# TTL_USB.net
KiCad netlist of a schematic drawn in Altium Designer
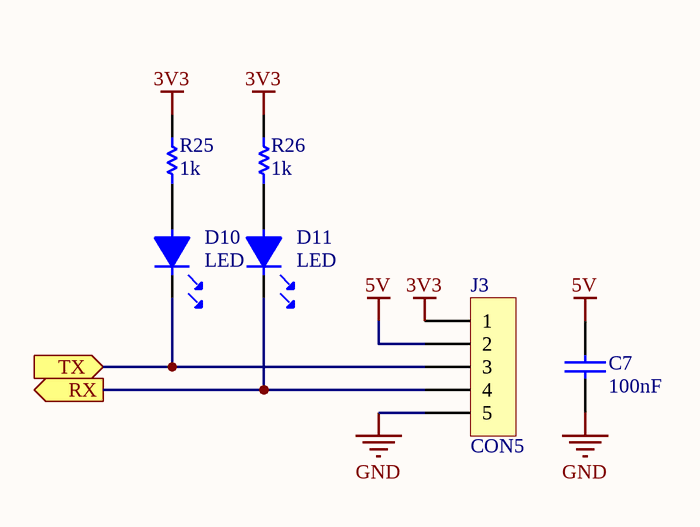
[diagram p0: TTL USB.SchDoc]

(export (version "E")
  (design (tool "Eeschema 10.0.6"))
  (components
    (comp (ref "C7") (value "100nF") (footprint "0805") (libsource (lib "LIBPIOIX") (part "CAP")))
    (comp (ref "D10") (value "LED") (footprint "LED0805") (libsource (lib "LIBPIOIX") (part "LED")))
    (comp (ref "D11") (value "LED") (footprint "LED0805") (libsource (lib "LIBPIOIX") (part "LED")))
    (comp (ref "J3") (value "CON5") (footprint "SIP5") (libsource (lib "LIBPIOIX") (part "CON5")))
    (comp (ref "R25") (value "1k") (footprint "0805") (libsource (lib "LIBPIOIX") (part "RES")))
    (comp (ref "R26") (value "1k") (footprint "0805") (libsource (lib "LIBPIOIX") (part "RES")))
  )
  (nets
    (net (code "1") (name "/RX") (class "Default")
      (node (ref "D11") (pin "2") (pinfunction "2_2") (pintype "passive"))
      (node (ref "J3") (pin "4") (pinfunction "4_4") (pintype "passive"))
    )
    (net (code "2") (name "/TX") (class "Default")
      (node (ref "D10") (pin "2") (pinfunction "2_2") (pintype "passive"))
      (node (ref "J3") (pin "3") (pinfunction "3_3") (pintype "passive"))
    )
    (net (code "3") (name "3V3") (class "Default")
      (node (ref "J3") (pin "1") (pinfunction "1_1") (pintype "passive"))
      (node (ref "R25") (pin "2") (pinfunction "2_2") (pintype "passive"))
      (node (ref "R26") (pin "2") (pinfunction "2_2") (pintype "passive"))
    )
    (net (code "4") (name "5V") (class "Default")
      (node (ref "C7") (pin "1") (pinfunction "1_1") (pintype "passive"))
      (node (ref "J3") (pin "2") (pinfunction "2_2") (pintype "passive"))
    )
    (net (code "5") (name "GND") (class "Default")
      (node (ref "C7") (pin "2") (pinfunction "2_2") (pintype "passive"))
      (node (ref "J3") (pin "5") (pinfunction "5_5") (pintype "passive"))
    )
    (net (code "6") (name "Net-(D10-Pad1)") (class "Default")
      (node (ref "D10") (pin "1") (pinfunction "1_1") (pintype "passive"))
      (node (ref "R25") (pin "1") (pinfunction "1_1") (pintype "passive"))
    )
    (net (code "7") (name "Net-(D11-Pad1)") (class "Default")
      (node (ref "D11") (pin "1") (pinfunction "1_1") (pintype "passive"))
      (node (ref "R26") (pin "1") (pinfunction "1_1") (pintype "passive"))
    )
  )
)
